# Sheet1.net
KiCad netlist of a schematic drawn in Altium Designer
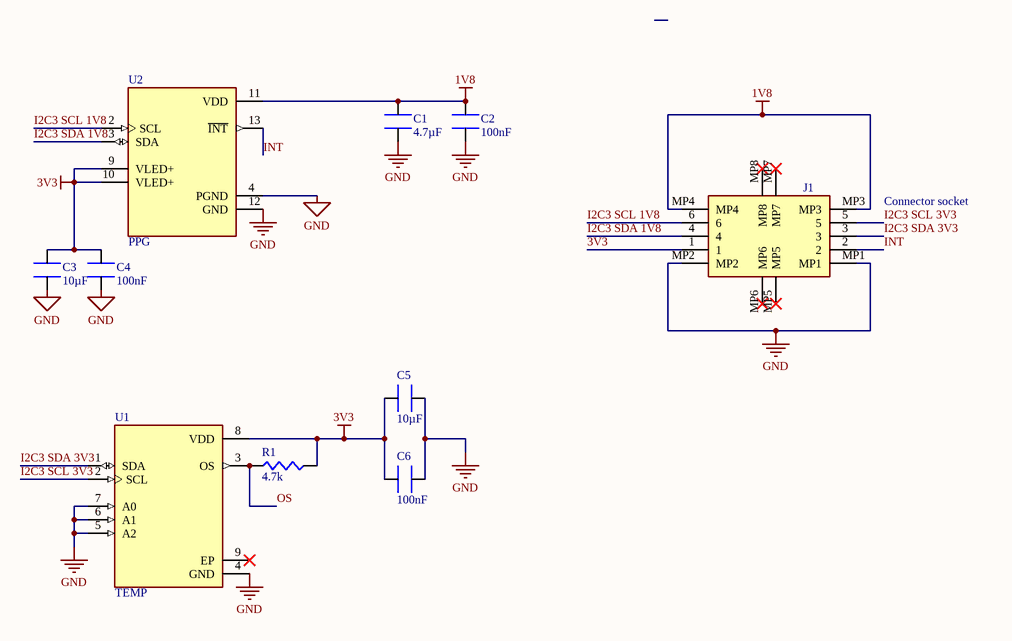
[diagram p0: Sheet1.SchDoc]

(export (version "E")
  (design (tool "Eeschema 10.0.6"))
  (components
    (comp (ref "C1")
      (value "4.7µF")
      (footprint "Chip2PinSM127P600-8N")
      (description "Condensatori in ceramica multistrato MLCC - SMD/SMT 6.3V 4.7uF X5R 0201 20%")
      (fields (field (name "TOLERANCE") "20%") (field (name "MANUFACTURER") "Kyocera AVX"))
      (libsource (lib "Narwhal_main") (part "CMP-001-00098-5"))
    )
    (comp (ref "C2")
      (value "100nF")
      (footprint "Chip2PinSM127P600-8N")
      (fields
        (field (name "MANUFACTURER") "KYOCERA AVX")
        (field (name "MANUFACTURER PART NUMBER") "0402YC104JAT4A")
      )
      (libsource (lib "Narwhal_main") (part "CMP-00047-1"))
    )
    (comp (ref "C3")
      (value "10µF")
      (footprint "Chip2PinSM127P600-8N")
      (fields
        (field (name "MANUFACTURER") "KYOCERA AVX")
        (field (name "MANUFACTURER PART NUMBER") "0402ZD106MAT2A")
      )
      (libsource (lib "Narwhal_main") (part "CMP-00044-1"))
    )
    (comp (ref "C4")
      (value "100nF")
      (footprint "Chip2PinSM127P600-8N")
      (fields
        (field (name "MANUFACTURER") "KYOCERA AVX")
        (field (name "MANUFACTURER PART NUMBER") "0402YC104JAT4A")
      )
      (libsource (lib "Narwhal_main") (part "CMP-00047-1"))
    )
    (comp (ref "C5")
      (value "10µF")
      (footprint "Chip2PinSM127P600-8N")
      (fields
        (field (name "MANUFACTURER") "KYOCERA AVX")
        (field (name "MANUFACTURER PART NUMBER") "0402ZD106MAT2A")
      )
      (libsource (lib "Narwhal_main") (part "CMP-00044-1"))
    )
    (comp (ref "C6")
      (value "100nF")
      (footprint "Chip2PinSM127P600-8N")
      (fields
        (field (name "MANUFACTURER") "KYOCERA AVX")
        (field (name "MANUFACTURER PART NUMBER") "0402YC104JAT4A")
      )
      (libsource (lib "Narwhal_main") (part "CMP-00047-1"))
    )
    (comp (ref "J1")
      (value "Connector socket")
      (footprint "BM29B066DS2035V53")
      (description "FFC & FPC Connectors")
      (fields
        (field (name "MOUSER PART NUMBER") "798-29B066DS/2035V53")
        (field (name "MANUFACTURER_PART_NUMBER") "BM29B0.6-6DS/2-0.35V(53)")
      )
      (libsource (lib "SWDP_proj") (part "BM29B0.6-6DS_2-0.35V_53_"))
    )
    (comp (ref "R1")
      (value "4.7k")
      (footprint "Chip2PinSM127P600-8N")
      (fields
        (field (name "TOLERANCE") "5%")
        (field (name "POWER") "50mW")
        (field (name "MANUFACTURER") "Bourns")
      )
      (libsource (lib "Narwhal_main") (part "CMP-00117-1"))
    )
    (comp (ref "U1")
      (value "TEMP")
      (footprint "SON65P300X300X80-9N")
      (description "Human Body Temperature Sensor")
      (fields (field (name "MF") "Analog Devices") (field (name "MP") "MAX30205MTA+T"))
      (libsource (lib "SWDP_proj") (part "MAX30205MTA+T"))
    )
    (comp (ref "U2")
      (value "PPG")
      (footprint "PSON80P560X330X165-14N")
      (description "Pulse Oximeter and Heart Rate Sensor Digital Output 1.8V 14-Pin OLGA T/R")
      (fields (field (name "MP") "MAX30101EFD+T") (field (name "DIGI-KEY_PART_NUMBER") "MAX30101EFD+TTR-ND"))
      (libsource (lib "SWDP_proj") (part "MAX30101EFD+T"))
    )
  )
  (nets
    (net (code "1") (name "/I2C3 SCL 1V8") (class "Default")
      (node (ref "J1") (pin "6") (pinfunction "6_6") (pintype "passive"))
      (node (ref "U2") (pin "2") (pinfunction "SCL_2") (pintype "input"))
    )
    (net (code "2") (name "/I2C3 SCL 3V3") (class "Default")
      (node (ref "J1") (pin "5") (pinfunction "5_5") (pintype "passive"))
      (node (ref "U1") (pin "2") (pinfunction "SCL_2") (pintype "input"))
    )
    (net (code "3") (name "/I2C3 SDA 1V8") (class "Default")
      (node (ref "J1") (pin "4") (pinfunction "4_4") (pintype "passive"))
      (node (ref "U2") (pin "3") (pinfunction "SDA_3") (pintype "bidirectional"))
    )
    (net (code "4") (name "/I2C3 SDA 3V3") (class "Default")
      (node (ref "J1") (pin "3") (pinfunction "3_3") (pintype "passive"))
      (node (ref "U1") (pin "1") (pinfunction "SDA_1") (pintype "bidirectional"))
    )
    (net (code "5") (name "/INT") (class "Default")
      (node (ref "J1") (pin "2") (pinfunction "2_2") (pintype "passive"))
      (node (ref "U2") (pin "13") (pinfunction "~{INT}_13") (pintype "output"))
    )
    (net (code "6") (name "/OS") (class "Default")
      (node (ref "R1") (pin "1") (pinfunction "1_1") (pintype "passive"))
      (node (ref "U1") (pin "3") (pinfunction "OS_3") (pintype "output"))
    )
    (net (code "7") (name "1V8") (class "Default")
      (node (ref "C1") (pin "2") (pinfunction "2_2") (pintype "passive"))
      (node (ref "C2") (pin "2") (pinfunction "2_2") (pintype "passive"))
      (node (ref "J1") (pin "MP3") (pinfunction "MP3_MP3") (pintype "passive"))
      (node (ref "J1") (pin "MP4") (pinfunction "MP4_MP4") (pintype "passive"))
      (node (ref "U2") (pin "11") (pinfunction "VDD_11") (pintype "power_in"))
    )
    (net (code "8") (name "3V3") (class "Default")
      (node (ref "C3") (pin "2") (pinfunction "2_2") (pintype "passive"))
      (node (ref "C4") (pin "2") (pinfunction "2_2") (pintype "passive"))
      (node (ref "C5") (pin "1") (pinfunction "1_1") (pintype "passive"))
      (node (ref "C6") (pin "1") (pinfunction "1_1") (pintype "passive"))
      (node (ref "J1") (pin "1") (pinfunction "1_1") (pintype "passive"))
      (node (ref "R1") (pin "2") (pinfunction "2_2") (pintype "passive"))
      (node (ref "U1") (pin "8") (pinfunction "VDD_8") (pintype "power_in"))
      (node (ref "U2") (pin "10") (pinfunction "VLED+_10") (pintype "passive"))
      (node (ref "U2") (pin "9") (pinfunction "VLED+_9") (pintype "passive"))
    )
    (net (code "9") (name "GND") (class "Default")
      (node (ref "C1") (pin "1") (pinfunction "1_1") (pintype "passive"))
      (node (ref "C2") (pin "1") (pinfunction "1_1") (pintype "passive"))
      (node (ref "C3") (pin "1") (pinfunction "1_1") (pintype "passive"))
      (node (ref "C4") (pin "1") (pinfunction "1_1") (pintype "passive"))
      (node (ref "C5") (pin "2") (pinfunction "2_2") (pintype "passive"))
      (node (ref "C6") (pin "2") (pinfunction "2_2") (pintype "passive"))
      (node (ref "J1") (pin "MP1") (pinfunction "MP1_MP1") (pintype "passive"))
      (node (ref "J1") (pin "MP2") (pinfunction "MP2_MP2") (pintype "passive"))
      (node (ref "U1") (pin "4") (pinfunction "GND_4") (pintype "power_in"))
      (node (ref "U1") (pin "5") (pinfunction "A2_5") (pintype "input"))
      (node (ref "U1") (pin "6") (pinfunction "A1_6") (pintype "input"))
      (node (ref "U1") (pin "7") (pinfunction "A0_7") (pintype "input"))
      (node (ref "U2") (pin "12") (pinfunction "GND_12") (pintype "power_in"))
      (node (ref "U2") (pin "4") (pinfunction "PGND_4") (pintype "power_in"))
    )
    (net (code "10") (name "unconnected-(J1-PadMP5)") (class "Default")
      (node (ref "J1") (pin "MP5") (pinfunction "MP5_MP5") (pintype "passive+no_connect"))
    )
    (net (code "11") (name "unconnected-(J1-PadMP6)") (class "Default")
      (node (ref "J1") (pin "MP6") (pinfunction "MP6_MP6") (pintype "passive+no_connect"))
    )
    (net (code "12") (name "unconnected-(J1-PadMP7)") (class "Default")
      (node (ref "J1") (pin "MP7") (pinfunction "MP7_MP7") (pintype "passive+no_connect"))
    )
    (net (code "13") (name "unconnected-(J1-PadMP8)") (class "Default")
      (node (ref "J1") (pin "MP8") (pinfunction "MP8_MP8") (pintype "passive+no_connect"))
    )
    (net (code "14") (name "unconnected-(U1-EP-Pad9)") (class "Default")
      (node (ref "U1") (pin "9") (pinfunction "EP_9") (pintype "power_in+no_connect"))
    )
  )
)
